# XILINX_ARTIX-7_FPGA_A704_Motherboard_CON.net
KiCad netlist of a schematic drawn in Altium Designer
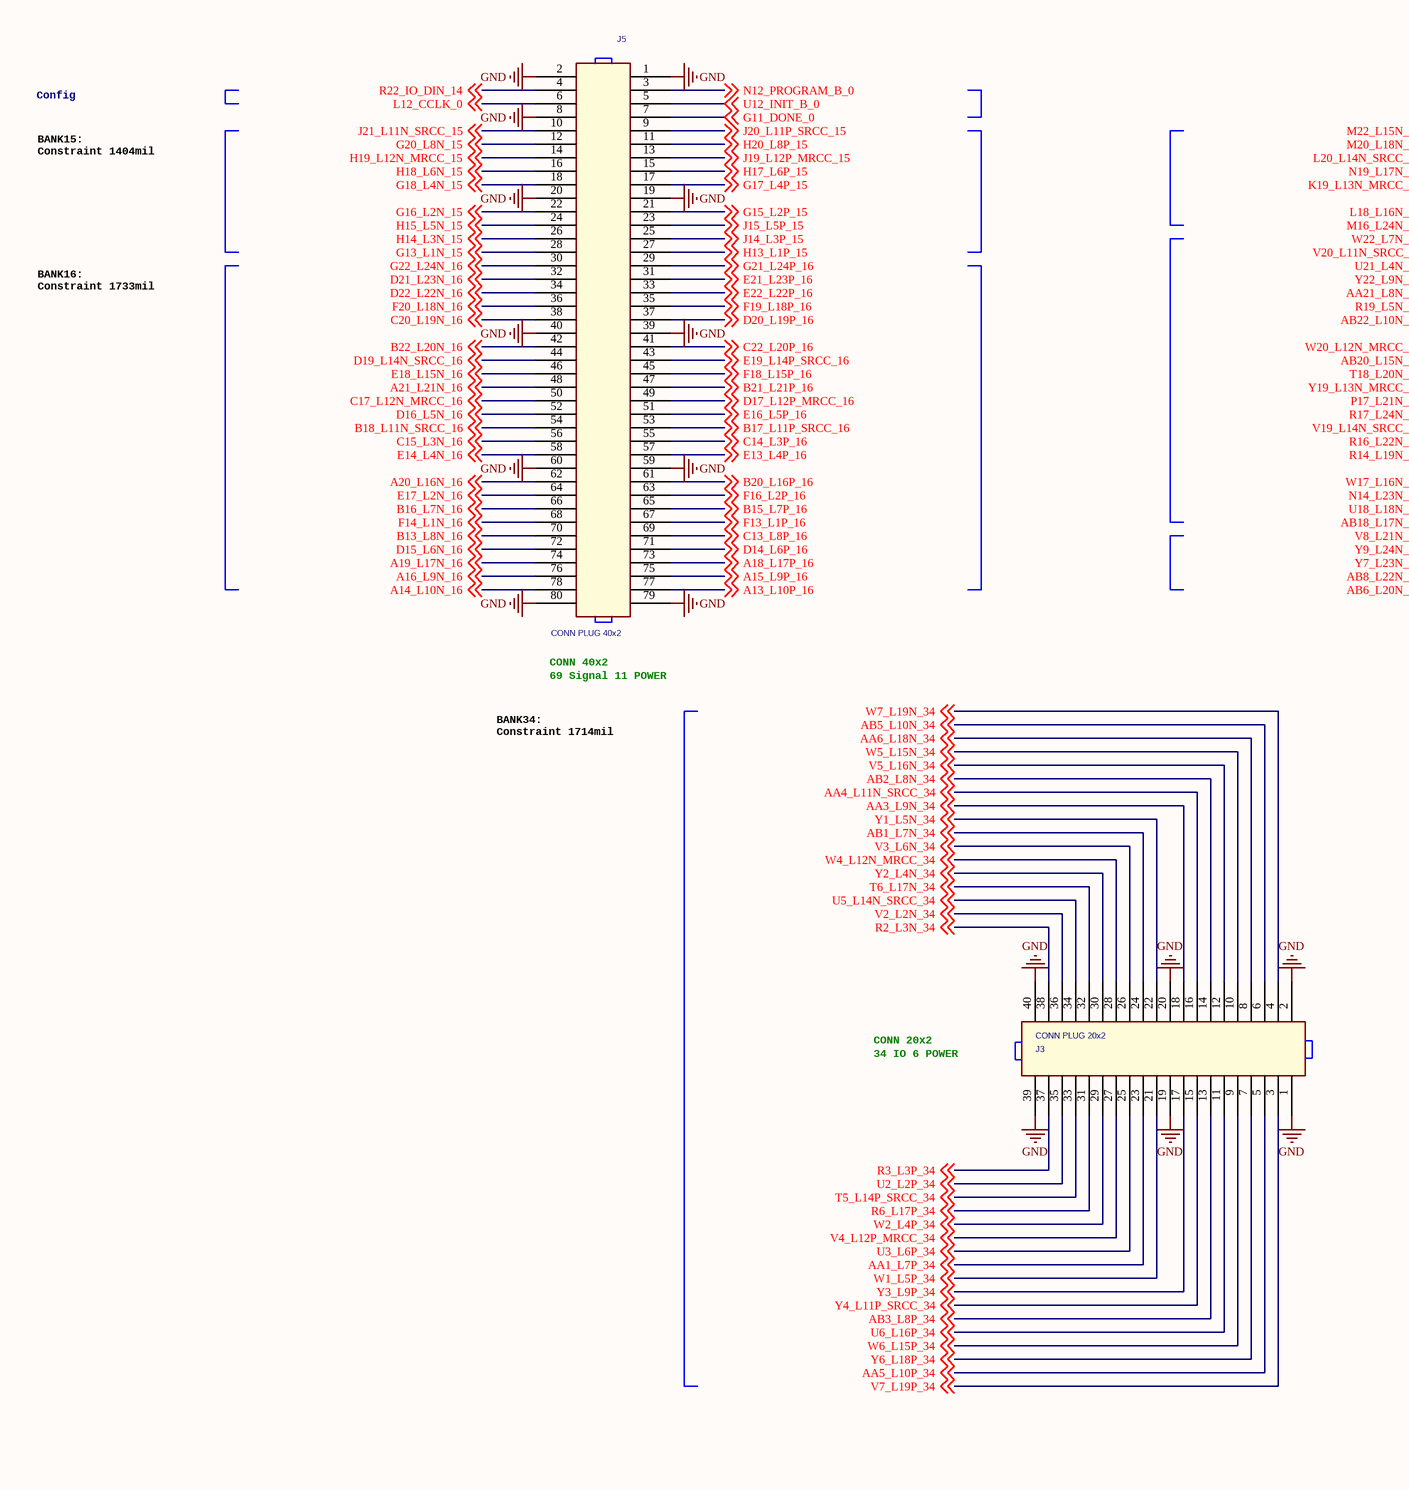
[diagram p0: XILINX ARTIX-7 FPGA A704 Motherboard_CON.SchDoc, left]
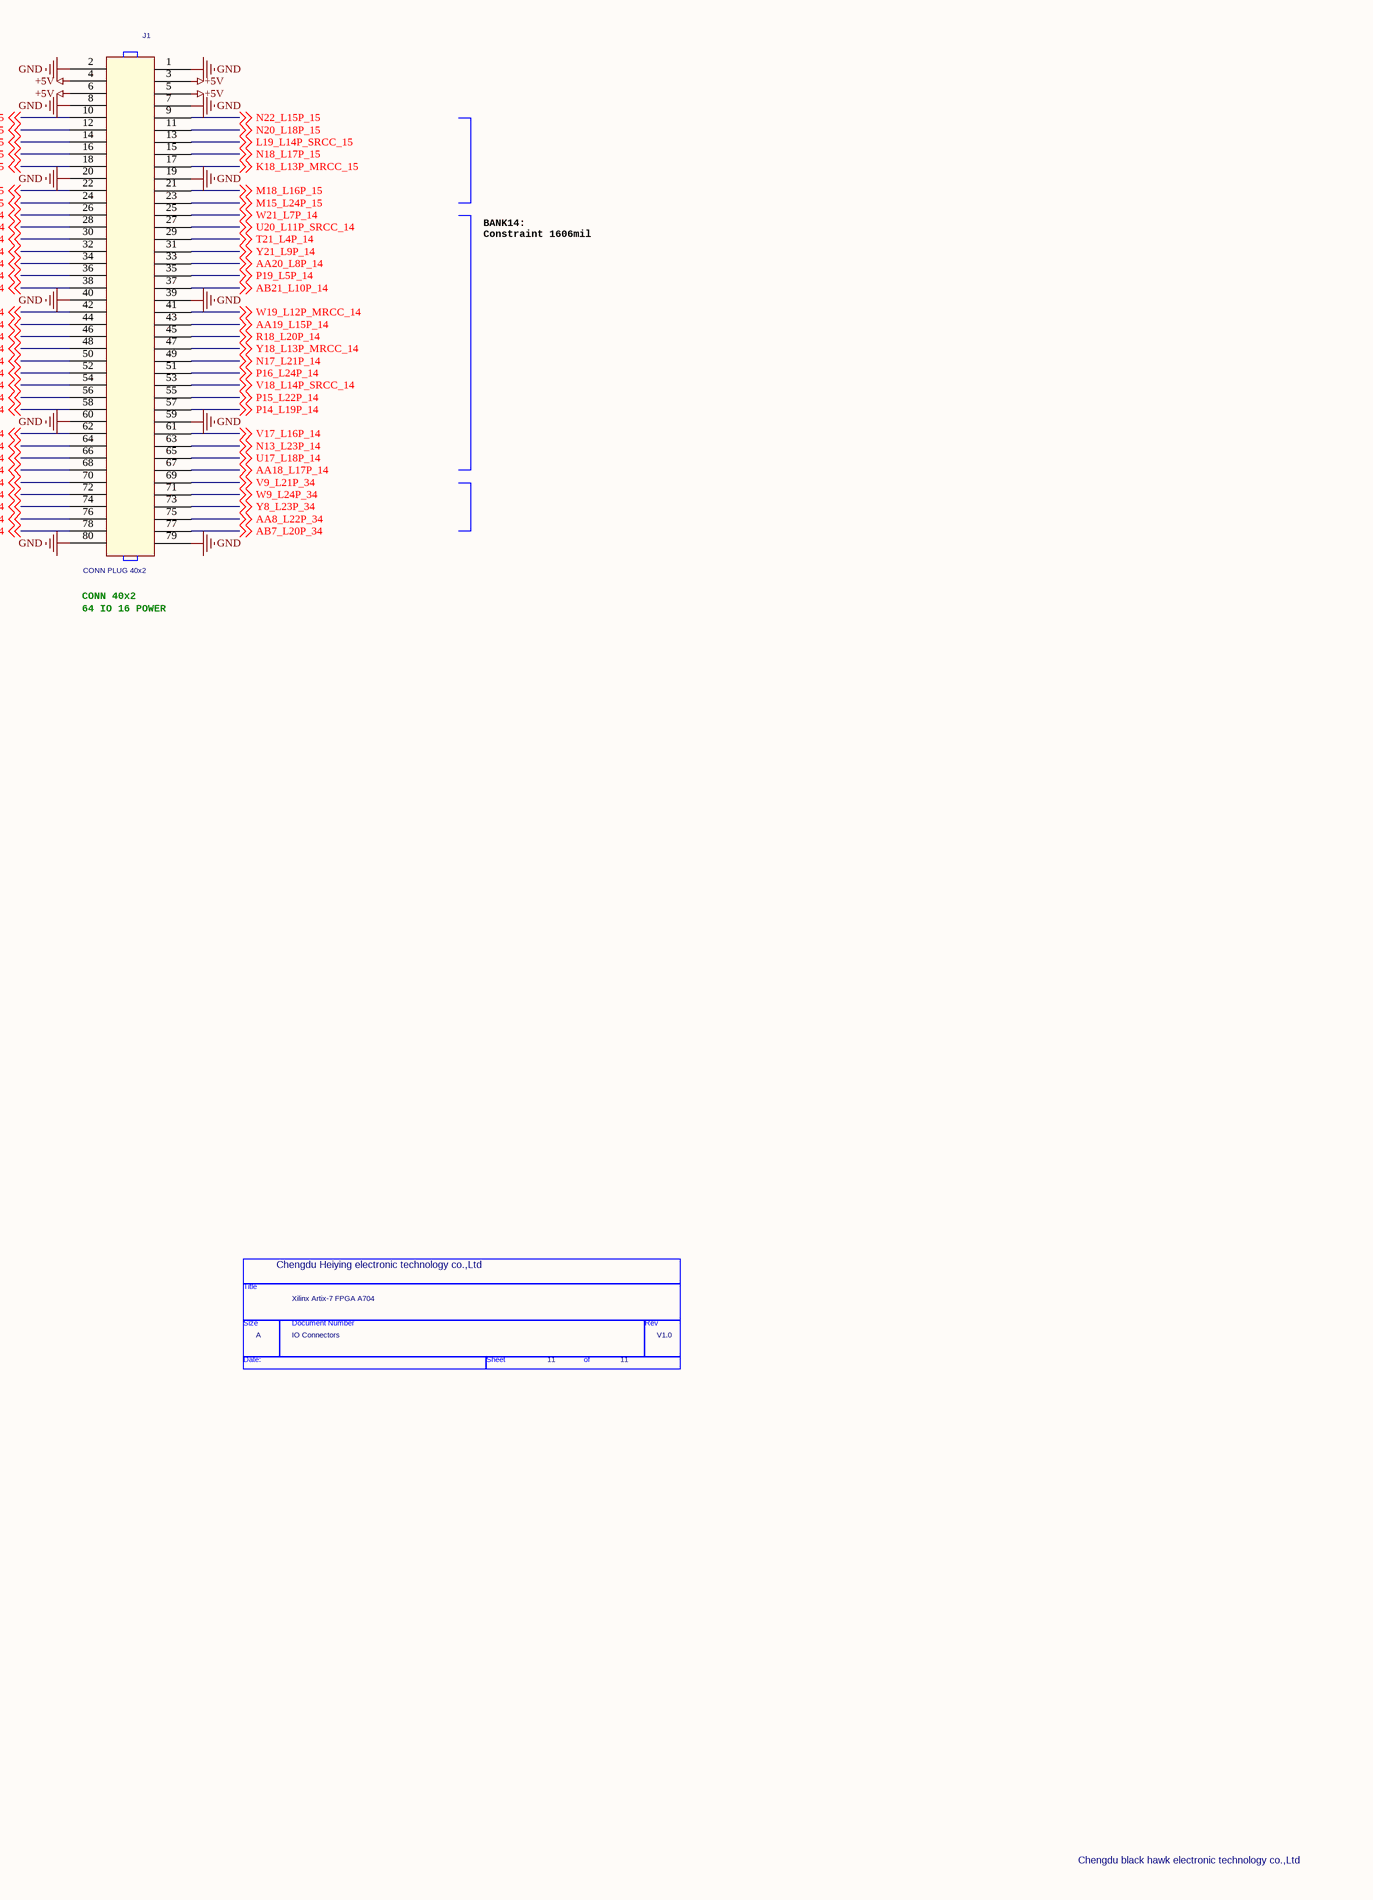
[diagram p1: XILINX ARTIX-7 FPGA A704 Motherboard_CON.SchDoc, right]

(export (version "E")
  (design (tool "Eeschema 10.0.6"))
  (components
    (comp (ref "*")
      (value "TitleBlock0")
      (fields
        (field (name "DOC") "IO Connectors")
        (field (name "REVCODE") "V1.0")
        (field (name "TITLE") "Xilinx Artix-7 FPGA A704")
        (field (name "PAGE SIZE") "A")
        (field (name "PAGE NUMBER") "11")
        (field (name "PAGE COUNT") "11")
      )
      (libsource (lib "*") (part "TitleBlock0"))
    )
    (comp (ref "J1") (value "CONN PLUG 40x2") (libsource (lib "*") (part "CONN PLUG 40x2")))
    (comp (ref "J3") (value "CONN PLUG 20x2") (libsource (lib "*") (part "CONN PLUG 20x2_0")))
    (comp (ref "J5") (value "CONN PLUG 40x2") (libsource (lib "*") (part "CONN PLUG 40x2")))
  )
  (nets
    (net (code "1") (name "+5V") (class "Default")
      (node (ref "J1") (pin "3") (pinfunction "3_3") (pintype "passive"))
      (node (ref "J1") (pin "4") (pinfunction "4_4") (pintype "passive"))
      (node (ref "J1") (pin "5") (pinfunction "5_5") (pintype "passive"))
      (node (ref "J1") (pin "6") (pinfunction "6_6") (pintype "passive"))
    )
    (net (code "2") (name "A13_L10P_16") (class "Default")
      (node (ref "J5") (pin "77") (pinfunction "77_77") (pintype "passive"))
    )
    (net (code "3") (name "A14_L10N_16") (class "Default")
      (node (ref "J5") (pin "78") (pinfunction "78_78") (pintype "passive"))
    )
    (net (code "4") (name "A15_L9P_16") (class "Default")
      (node (ref "J5") (pin "75") (pinfunction "75_75") (pintype "passive"))
    )
    (net (code "5") (name "A16_L9N_16") (class "Default")
      (node (ref "J5") (pin "76") (pinfunction "76_76") (pintype "passive"))
    )
    (net (code "6") (name "A18_L17P_16") (class "Default")
      (node (ref "J5") (pin "73") (pinfunction "73_73") (pintype "passive"))
    )
    (net (code "7") (name "A19_L17N_16") (class "Default")
      (node (ref "J5") (pin "74") (pinfunction "74_74") (pintype "passive"))
    )
    (net (code "8") (name "A20_L16N_16") (class "Default")
      (node (ref "J5") (pin "62") (pinfunction "62_62") (pintype "passive"))
    )
    (net (code "9") (name "A21_L21N_16") (class "Default")
      (node (ref "J5") (pin "48") (pinfunction "48_48") (pintype "passive"))
    )
    (net (code "10") (name "AA1_L7P_34") (class "Default")
      (node (ref "J3") (pin "23") (pinfunction "23_23") (pintype "passive"))
    )
    (net (code "11") (name "AA3_L9N_34") (class "Default")
      (node (ref "J3") (pin "18") (pinfunction "18_18") (pintype "passive"))
    )
    (net (code "12") (name "AA4_L11N_SRCC_34") (class "Default")
      (node (ref "J3") (pin "16") (pinfunction "16_16") (pintype "passive"))
    )
    (net (code "13") (name "AA5_L10P_34") (class "Default")
      (node (ref "J3") (pin "5") (pinfunction "5_5") (pintype "passive"))
    )
    (net (code "14") (name "AA6_L18N_34") (class "Default")
      (node (ref "J3") (pin "8") (pinfunction "8_8") (pintype "passive"))
    )
    (net (code "15") (name "AA8_L22P_34") (class "Default")
      (node (ref "J1") (pin "75") (pinfunction "75_75") (pintype "passive"))
    )
    (net (code "16") (name "AA18_L17P_14") (class "Default")
      (node (ref "J1") (pin "67") (pinfunction "67_67") (pintype "passive"))
    )
    (net (code "17") (name "AA19_L15P_14") (class "Default")
      (node (ref "J1") (pin "43") (pinfunction "43_43") (pintype "passive"))
    )
    (net (code "18") (name "AA20_L8P_14") (class "Default")
      (node (ref "J1") (pin "33") (pinfunction "33_33") (pintype "passive"))
    )
    (net (code "19") (name "AA21_L8N_14") (class "Default")
      (node (ref "J1") (pin "34") (pinfunction "34_34") (pintype "passive"))
    )
    (net (code "20") (name "AB1_L7N_34") (class "Default")
      (node (ref "J3") (pin "24") (pinfunction "24_24") (pintype "passive"))
    )
    (net (code "21") (name "AB2_L8N_34") (class "Default")
      (node (ref "J3") (pin "14") (pinfunction "14_14") (pintype "passive"))
    )
    (net (code "22") (name "AB3_L8P_34") (class "Default")
      (node (ref "J3") (pin "13") (pinfunction "13_13") (pintype "passive"))
    )
    (net (code "23") (name "AB5_L10N_34") (class "Default")
      (node (ref "J3") (pin "6") (pinfunction "6_6") (pintype "passive"))
    )
    (net (code "24") (name "AB6_L20N_34") (class "Default")
      (node (ref "J1") (pin "78") (pinfunction "78_78") (pintype "passive"))
    )
    (net (code "25") (name "AB7_L20P_34") (class "Default")
      (node (ref "J1") (pin "77") (pinfunction "77_77") (pintype "passive"))
    )
    (net (code "26") (name "AB8_L22N_34") (class "Default")
      (node (ref "J1") (pin "76") (pinfunction "76_76") (pintype "passive"))
    )
    (net (code "27") (name "AB18_L17N_14") (class "Default")
      (node (ref "J1") (pin "68") (pinfunction "68_68") (pintype "passive"))
    )
    (net (code "28") (name "AB20_L15N_14") (class "Default")
      (node (ref "J1") (pin "44") (pinfunction "44_44") (pintype "passive"))
    )
    (net (code "29") (name "AB21_L10P_14") (class "Default")
      (node (ref "J1") (pin "37") (pinfunction "37_37") (pintype "passive"))
    )
    (net (code "30") (name "AB22_L10N_14") (class "Default")
      (node (ref "J1") (pin "38") (pinfunction "38_38") (pintype "passive"))
    )
    (net (code "31") (name "B13_L8N_16") (class "Default")
      (node (ref "J5") (pin "70") (pinfunction "70_70") (pintype "passive"))
    )
    (net (code "32") (name "B15_L7P_16") (class "Default")
      (node (ref "J5") (pin "65") (pinfunction "65_65") (pintype "passive"))
    )
    (net (code "33") (name "B16_L7N_16") (class "Default")
      (node (ref "J5") (pin "66") (pinfunction "66_66") (pintype "passive"))
    )
    (net (code "34") (name "B17_L11P_SRCC_16") (class "Default")
      (node (ref "J5") (pin "53") (pinfunction "53_53") (pintype "passive"))
    )
    (net (code "35") (name "B18_L11N_SRCC_16") (class "Default")
      (node (ref "J5") (pin "54") (pinfunction "54_54") (pintype "passive"))
    )
    (net (code "36") (name "B20_L16P_16") (class "Default")
      (node (ref "J5") (pin "61") (pinfunction "61_61") (pintype "passive"))
    )
    (net (code "37") (name "B21_L21P_16") (class "Default")
      (node (ref "J5") (pin "47") (pinfunction "47_47") (pintype "passive"))
    )
    (net (code "38") (name "B22_L20N_16") (class "Default")
      (node (ref "J5") (pin "42") (pinfunction "42_42") (pintype "passive"))
    )
    (net (code "39") (name "C13_L8P_16") (class "Default")
      (node (ref "J5") (pin "69") (pinfunction "69_69") (pintype "passive"))
    )
    (net (code "40") (name "C14_L3P_16") (class "Default")
      (node (ref "J5") (pin "55") (pinfunction "55_55") (pintype "passive"))
    )
    (net (code "41") (name "C15_L3N_16") (class "Default")
      (node (ref "J5") (pin "56") (pinfunction "56_56") (pintype "passive"))
    )
    (net (code "42") (name "C17_L12N_MRCC_16") (class "Default")
      (node (ref "J5") (pin "50") (pinfunction "50_50") (pintype "passive"))
    )
    (net (code "43") (name "C20_L19N_16") (class "Default")
      (node (ref "J5") (pin "38") (pinfunction "38_38") (pintype "passive"))
    )
    (net (code "44") (name "C22_L20P_16") (class "Default")
      (node (ref "J5") (pin "41") (pinfunction "41_41") (pintype "passive"))
    )
    (net (code "45") (name "D14_L6P_16") (class "Default")
      (node (ref "J5") (pin "71") (pinfunction "71_71") (pintype "passive"))
    )
    (net (code "46") (name "D15_L6N_16") (class "Default")
      (node (ref "J5") (pin "72") (pinfunction "72_72") (pintype "passive"))
    )
    (net (code "47") (name "D16_L5N_16") (class "Default")
      (node (ref "J5") (pin "52") (pinfunction "52_52") (pintype "passive"))
    )
    (net (code "48") (name "D17_L12P_MRCC_16") (class "Default")
      (node (ref "J5") (pin "49") (pinfunction "49_49") (pintype "passive"))
    )
    (net (code "49") (name "D19_L14N_SRCC_16") (class "Default")
      (node (ref "J5") (pin "44") (pinfunction "44_44") (pintype "passive"))
    )
    (net (code "50") (name "D20_L19P_16") (class "Default")
      (node (ref "J5") (pin "37") (pinfunction "37_37") (pintype "passive"))
    )
    (net (code "51") (name "D21_L23N_16") (class "Default")
      (node (ref "J5") (pin "32") (pinfunction "32_32") (pintype "passive"))
    )
    (net (code "52") (name "D22_L22N_16") (class "Default")
      (node (ref "J5") (pin "34") (pinfunction "34_34") (pintype "passive"))
    )
    (net (code "53") (name "E13_L4P_16") (class "Default")
      (node (ref "J5") (pin "57") (pinfunction "57_57") (pintype "passive"))
    )
    (net (code "54") (name "E14_L4N_16") (class "Default")
      (node (ref "J5") (pin "58") (pinfunction "58_58") (pintype "passive"))
    )
    (net (code "55") (name "E16_L5P_16") (class "Default")
      (node (ref "J5") (pin "51") (pinfunction "51_51") (pintype "passive"))
    )
    (net (code "56") (name "E17_L2N_16") (class "Default")
      (node (ref "J5") (pin "64") (pinfunction "64_64") (pintype "passive"))
    )
    (net (code "57") (name "E18_L15N_16") (class "Default")
      (node (ref "J5") (pin "46") (pinfunction "46_46") (pintype "passive"))
    )
    (net (code "58") (name "E19_L14P_SRCC_16") (class "Default")
      (node (ref "J5") (pin "43") (pinfunction "43_43") (pintype "passive"))
    )
    (net (code "59") (name "E21_L23P_16") (class "Default")
      (node (ref "J5") (pin "31") (pinfunction "31_31") (pintype "passive"))
    )
    (net (code "60") (name "E22_L22P_16") (class "Default")
      (node (ref "J5") (pin "33") (pinfunction "33_33") (pintype "passive"))
    )
    (net (code "61") (name "F13_L1P_16") (class "Default")
      (node (ref "J5") (pin "67") (pinfunction "67_67") (pintype "passive"))
    )
    (net (code "62") (name "F14_L1N_16") (class "Default")
      (node (ref "J5") (pin "68") (pinfunction "68_68") (pintype "passive"))
    )
    (net (code "63") (name "F16_L2P_16") (class "Default")
      (node (ref "J5") (pin "63") (pinfunction "63_63") (pintype "passive"))
    )
    (net (code "64") (name "F18_L15P_16") (class "Default")
      (node (ref "J5") (pin "45") (pinfunction "45_45") (pintype "passive"))
    )
    (net (code "65") (name "F19_L18P_16") (class "Default")
      (node (ref "J5") (pin "35") (pinfunction "35_35") (pintype "passive"))
    )
    (net (code "66") (name "F20_L18N_16") (class "Default")
      (node (ref "J5") (pin "36") (pinfunction "36_36") (pintype "passive"))
    )
    (net (code "67") (name "G11_DONE_0") (class "Default")
      (node (ref "J5") (pin "7") (pinfunction "7_7") (pintype "passive"))
    )
    (net (code "68") (name "G13_L1N_15") (class "Default")
      (node (ref "J5") (pin "28") (pinfunction "28_28") (pintype "passive"))
    )
    (net (code "69") (name "G15_L2P_15") (class "Default")
      (node (ref "J5") (pin "21") (pinfunction "21_21") (pintype "passive"))
    )
    (net (code "70") (name "G16_L2N_15") (class "Default")
      (node (ref "J5") (pin "22") (pinfunction "22_22") (pintype "passive"))
    )
    (net (code "71") (name "G17_L4P_15") (class "Default")
      (node (ref "J5") (pin "17") (pinfunction "17_17") (pintype "passive"))
    )
    (net (code "72") (name "G18_L4N_15") (class "Default")
      (node (ref "J5") (pin "18") (pinfunction "18_18") (pintype "passive"))
    )
    (net (code "73") (name "G20_L8N_15") (class "Default")
      (node (ref "J5") (pin "12") (pinfunction "12_12") (pintype "passive"))
    )
    (net (code "74") (name "G21_L24P_16") (class "Default")
      (node (ref "J5") (pin "29") (pinfunction "29_29") (pintype "passive"))
    )
    (net (code "75") (name "G22_L24N_16") (class "Default")
      (node (ref "J5") (pin "30") (pinfunction "30_30") (pintype "passive"))
    )
    (net (code "76") (name "GND") (class "Default")
      (node (ref "J1") (pin "1") (pinfunction "1_1") (pintype "passive"))
      (node (ref "J1") (pin "19") (pinfunction "19_19") (pintype "passive"))
      (node (ref "J1") (pin "2") (pinfunction "2_2") (pintype "passive"))
      (node (ref "J1") (pin "20") (pinfunction "20_20") (pintype "passive"))
      (node (ref "J1") (pin "39") (pinfunction "39_39") (pintype "passive"))
      (node (ref "J1") (pin "40") (pinfunction "40_40") (pintype "passive"))
      (node (ref "J1") (pin "59") (pinfunction "59_59") (pintype "passive"))
      (node (ref "J1") (pin "60") (pinfunction "60_60") (pintype "passive"))
      (node (ref "J1") (pin "7") (pinfunction "7_7") (pintype "passive"))
      (node (ref "J1") (pin "79") (pinfunction "79_79") (pintype "passive"))
      (node (ref "J1") (pin "8") (pinfunction "8_8") (pintype "passive"))
      (node (ref "J1") (pin "80") (pinfunction "80_80") (pintype "passive"))
      (node (ref "J3") (pin "1") (pinfunction "1_1") (pintype "passive"))
      (node (ref "J3") (pin "19") (pinfunction "19_19") (pintype "passive"))
      (node (ref "J3") (pin "2") (pinfunction "2_2") (pintype "passive"))
      (node (ref "J3") (pin "20") (pinfunction "20_20") (pintype "passive"))
      (node (ref "J3") (pin "39") (pinfunction "39_39") (pintype "passive"))
      (node (ref "J3") (pin "40") (pinfunction "40_40") (pintype "passive"))
      (node (ref "J5") (pin "1") (pinfunction "1_1") (pintype "passive"))
      (node (ref "J5") (pin "19") (pinfunction "19_19") (pintype "passive"))
      (node (ref "J5") (pin "2") (pinfunction "2_2") (pintype "passive"))
      (node (ref "J5") (pin "20") (pinfunction "20_20") (pintype "passive"))
      (node (ref "J5") (pin "39") (pinfunction "39_39") (pintype "passive"))
      (node (ref "J5") (pin "40") (pinfunction "40_40") (pintype "passive"))
      (node (ref "J5") (pin "59") (pinfunction "59_59") (pintype "passive"))
      (node (ref "J5") (pin "60") (pinfunction "60_60") (pintype "passive"))
      (node (ref "J5") (pin "79") (pinfunction "79_79") (pintype "passive"))
      (node (ref "J5") (pin "8") (pinfunction "8_8") (pintype "passive"))
      (node (ref "J5") (pin "80") (pinfunction "80_80") (pintype "passive"))
    )
    (net (code "77") (name "H13_L1P_15") (class "Default")
      (node (ref "J5") (pin "27") (pinfunction "27_27") (pintype "passive"))
    )
    (net (code "78") (name "H14_L3N_15") (class "Default")
      (node (ref "J5") (pin "26") (pinfunction "26_26") (pintype "passive"))
    )
    (net (code "79") (name "H15_L5N_15") (class "Default")
      (node (ref "J5") (pin "24") (pinfunction "24_24") (pintype "passive"))
    )
    (net (code "80") (name "H17_L6P_15") (class "Default")
      (node (ref "J5") (pin "15") (pinfunction "15_15") (pintype "passive"))
    )
    (net (code "81") (name "H18_L6N_15") (class "Default")
      (node (ref "J5") (pin "16") (pinfunction "16_16") (pintype "passive"))
    )
    (net (code "82") (name "H19_L12N_MRCC_15") (class "Default")
      (node (ref "J5") (pin "14") (pinfunction "14_14") (pintype "passive"))
    )
    (net (code "83") (name "H20_L8P_15") (class "Default")
      (node (ref "J5") (pin "11") (pinfunction "11_11") (pintype "passive"))
    )
    (net (code "84") (name "J14_L3P_15") (class "Default")
      (node (ref "J5") (pin "25") (pinfunction "25_25") (pintype "passive"))
    )
    (net (code "85") (name "J15_L5P_15") (class "Default")
      (node (ref "J5") (pin "23") (pinfunction "23_23") (pintype "passive"))
    )
    (net (code "86") (name "J19_L12P_MRCC_15") (class "Default")
      (node (ref "J5") (pin "13") (pinfunction "13_13") (pintype "passive"))
    )
    (net (code "87") (name "J20_L11P_SRCC_15") (class "Default")
      (node (ref "J5") (pin "9") (pinfunction "9_9") (pintype "passive"))
    )
    (net (code "88") (name "J21_L11N_SRCC_15") (class "Default")
      (node (ref "J5") (pin "10") (pinfunction "10_10") (pintype "passive"))
    )
    (net (code "89") (name "K18_L13P_MRCC_15") (class "Default")
      (node (ref "J1") (pin "17") (pinfunction "17_17") (pintype "passive"))
    )
    (net (code "90") (name "K19_L13N_MRCC_15") (class "Default")
      (node (ref "J1") (pin "18") (pinfunction "18_18") (pintype "passive"))
    )
    (net (code "91") (name "L12_CCLK_0") (class "Default")
      (node (ref "J5") (pin "6") (pinfunction "6_6") (pintype "passive"))
    )
    (net (code "92") (name "L18_L16N_15") (class "Default")
      (node (ref "J1") (pin "22") (pinfunction "22_22") (pintype "passive"))
    )
    (net (code "93") (name "L19_L14P_SRCC_15") (class "Default")
      (node (ref "J1") (pin "13") (pinfunction "13_13") (pintype "passive"))
    )
    (net (code "94") (name "L20_L14N_SRCC_15") (class "Default")
      (node (ref "J1") (pin "14") (pinfunction "14_14") (pintype "passive"))
    )
    (net (code "95") (name "M15_L24P_15") (class "Default")
      (node (ref "J1") (pin "23") (pinfunction "23_23") (pintype "passive"))
    )
    (net (code "96") (name "M16_L24N_15") (class "Default")
      (node (ref "J1") (pin "24") (pinfunction "24_24") (pintype "passive"))
    )
    (net (code "97") (name "M18_L16P_15") (class "Default")
      (node (ref "J1") (pin "21") (pinfunction "21_21") (pintype "passive"))
    )
    (net (code "98") (name "M20_L18N_15") (class "Default")
      (node (ref "J1") (pin "12") (pinfunction "12_12") (pintype "passive"))
    )
    (net (code "99") (name "M22_L15N_15") (class "Default")
      (node (ref "J1") (pin "10") (pinfunction "10_10") (pintype "passive"))
    )
    (net (code "100") (name "N12_PROGRAM_B_0") (class "Default")
      (node (ref "J5") (pin "3") (pinfunction "3_3") (pintype "passive"))
    )
    (net (code "101") (name "N13_L23P_14") (class "Default")
      (node (ref "J1") (pin "63") (pinfunction "63_63") (pintype "passive"))
    )
    (net (code "102") (name "N14_L23N_14") (class "Default")
      (node (ref "J1") (pin "64") (pinfunction "64_64") (pintype "passive"))
    )
    (net (code "103") (name "N17_L21P_14") (class "Default")
      (node (ref "J1") (pin "49") (pinfunction "49_49") (pintype "passive"))
    )
    (net (code "104") (name "N18_L17P_15") (class "Default")
      (node (ref "J1") (pin "15") (pinfunction "15_15") (pintype "passive"))
    )
    (net (code "105") (name "N19_L17N_15") (class "Default")
      (node (ref "J1") (pin "16") (pinfunction "16_16") (pintype "passive"))
    )
    (net (code "106") (name "N20_L18P_15") (class "Default")
      (node (ref "J1") (pin "11") (pinfunction "11_11") (pintype "passive"))
    )
    (net (code "107") (name "N22_L15P_15") (class "Default")
      (node (ref "J1") (pin "9") (pinfunction "9_9") (pintype "passive"))
    )
    (net (code "108") (name "P14_L19P_14") (class "Default")
      (node (ref "J1") (pin "57") (pinfunction "57_57") (pintype "passive"))
    )
    (net (code "109") (name "P15_L22P_14") (class "Default")
      (node (ref "J1") (pin "55") (pinfunction "55_55") (pintype "passive"))
    )
    (net (code "110") (name "P16_L24P_14") (class "Default")
      (node (ref "J1") (pin "51") (pinfunction "51_51") (pintype "passive"))
    )
    (net (code "111") (name "P17_L21N_14") (class "Default")
      (node (ref "J1") (pin "50") (pinfunction "50_50") (pintype "passive"))
    )
    (net (code "112") (name "P19_L5P_14") (class "Default")
      (node (ref "J1") (pin "35") (pinfunction "35_35") (pintype "passive"))
    )
    (net (code "113") (name "R2_L3N_34") (class "Default")
      (node (ref "J3") (pin "38") (pinfunction "38_38") (pintype "passive"))
    )
    (net (code "114") (name "R3_L3P_34") (class "Default")
      (node (ref "J3") (pin "37") (pinfunction "37_37") (pintype "passive"))
    )
    (net (code "115") (name "R6_L17P_34") (class "Default")
      (node (ref "J3") (pin "31") (pinfunction "31_31") (pintype "passive"))
    )
    (net (code "116") (name "R14_L19N_14") (class "Default")
      (node (ref "J1") (pin "58") (pinfunction "58_58") (pintype "passive"))
    )
    (net (code "117") (name "R16_L22N_14") (class "Default")
      (node (ref "J1") (pin "56") (pinfunction "56_56") (pintype "passive"))
    )
    (net (code "118") (name "R17_L24N_14") (class "Default")
      (node (ref "J1") (pin "52") (pinfunction "52_52") (pintype "passive"))
    )
    (net (code "119") (name "R18_L20P_14") (class "Default")
      (node (ref "J1") (pin "45") (pinfunction "45_45") (pintype "passive"))
    )
    (net (code "120") (name "R19_L5N_14") (class "Default")
      (node (ref "J1") (pin "36") (pinfunction "36_36") (pintype "passive"))
    )
    (net (code "121") (name "R22_IO_DIN_14") (class "Default")
      (node (ref "J5") (pin "4") (pinfunction "4_4") (pintype "passive"))
    )
    (net (code "122") (name "T5_L14P_SRCC_34") (class "Default")
      (node (ref "J3") (pin "33") (pinfunction "33_33") (pintype "passive"))
    )
    (net (code "123") (name "T6_L17N_34") (class "Default")
      (node (ref "J3") (pin "32") (pinfunction "32_32") (pintype "passive"))
    )
    (net (code "124") (name "T18_L20N_14") (class "Default")
      (node (ref "J1") (pin "46") (pinfunction "46_46") (pintype "passive"))
    )
    (net (code "125") (name "T21_L4P_14") (class "Default")
      (node (ref "J1") (pin "29") (pinfunction "29_29") (pintype "passive"))
    )
    (net (code "126") (name "U2_L2P_34") (class "Default")
      (node (ref "J3") (pin "35") (pinfunction "35_35") (pintype "passive"))
    )
    (net (code "127") (name "U3_L6P_34") (class "Default")
      (node (ref "J3") (pin "25") (pinfunction "25_25") (pintype "passive"))
    )
    (net (code "128") (name "U5_L14N_SRCC_34") (class "Default")
      (node (ref "J3") (pin "34") (pinfunction "34_34") (pintype "passive"))
    )
    (net (code "129") (name "U6_L16P_34") (class "Default")
      (node (ref "J3") (pin "11") (pinfunction "11_11") (pintype "passive"))
    )
    (net (code "130") (name "U12_INIT_B_0") (class "Default")
      (node (ref "J5") (pin "5") (pinfunction "5_5") (pintype "passive"))
    )
    (net (code "131") (name "U17_L18P_14") (class "Default")
      (node (ref "J1") (pin "65") (pinfunction "65_65") (pintype "passive"))
    )
    (net (code "132") (name "U18_L18N_14") (class "Default")
      (node (ref "J1") (pin "66") (pinfunction "66_66") (pintype "passive"))
    )
    (net (code "133") (name "U20_L11P_SRCC_14") (class "Default")
      (node (ref "J1") (pin "27") (pinfunction "27_27") (pintype "passive"))
    )
    (net (code "134") (name "U21_L4N_14") (class "Default")
      (node (ref "J1") (pin "30") (pinfunction "30_30") (pintype "passive"))
    )
    (net (code "135") (name "V2_L2N_34") (class "Default")
      (node (ref "J3") (pin "36") (pinfunction "36_36") (pintype "passive"))
    )
    (net (code "136") (name "V3_L6N_34") (class "Default")
      (node (ref "J3") (pin "26") (pinfunction "26_26") (pintype "passive"))
    )
    (net (code "137") (name "V4_L12P_MRCC_34") (class "Default")
      (node (ref "J3") (pin "27") (pinfunction "27_27") (pintype "passive"))
    )
    (net (code "138") (name "V5_L16N_34") (class "Default")
      (node (ref "J3") (pin "12") (pinfunction "12_12") (pintype "passive"))
    )
    (net (code "139") (name "V7_L19P_34") (class "Default")
      (node (ref "J3") (pin "3") (pinfunction "3_3") (pintype "passive"))
    )
    (net (code "140") (name "V8_L21N_34") (class "Default")
      (node (ref "J1") (pin "70") (pinfunction "70_70") (pintype "passive"))
    )
    (net (code "141") (name "V9_L21P_34") (class "Default")
      (node (ref "J1") (pin "69") (pinfunction "69_69") (pintype "passive"))
    )
    (net (code "142") (name "V17_L16P_14") (class "Default")
      (node (ref "J1") (pin "61") (pinfunction "61_61") (pintype "passive"))
    )
    (net (code "143") (name "V18_L14P_SRCC_14") (class "Default")
      (node (ref "J1") (pin "53") (pinfunction "53_53") (pintype "passive"))
    )
    (net (code "144") (name "V19_L14N_SRCC_14") (class "Default")
      (node (ref "J1") (pin "54") (pinfunction "54_54") (pintype "passive"))
    )
    (net (code "145") (name "V20_L11N_SRCC_14") (class "Default")
      (node (ref "J1") (pin "28") (pinfunction "28_28") (pintype "passive"))
    )
    (net (code "146") (name "W1_L5P_34") (class "Default")
      (node (ref "J3") (pin "21") (pinfunction "21_21") (pintype "passive"))
    )
    (net (code "147") (name "W2_L4P_34") (class "Default")
      (node (ref "J3") (pin "29") (pinfunction "29_29") (pintype "passive"))
    )
    (net (code "148") (name "W4_L12N_MRCC_34") (class "Default")
      (node (ref "J3") (pin "28") (pinfunction "28_28") (pintype "passive"))
    )
    (net (code "149") (name "W5_L15N_34") (class "Default")
      (node (ref "J3") (pin "10") (pinfunction "10_10") (pintype "passive"))
    )
    (net (code "150") (name "W6_L15P_34") (class "Default")
      (node (ref "J3") (pin "9") (pinfunction "9_9") (pintype "passive"))
    )
    (net (code "151") (name "W7_L19N_34") (class "Default")
      (node (ref "J3") (pin "4") (pinfunction "4_4") (pintype "passive"))
    )
    (net (code "152") (name "W9_L24P_34") (class "Default")
      (node (ref "J1") (pin "71") (pinfunction "71_71") (pintype "passive"))
    )
    (net (code "153") (name "W17_L16N_14") (class "Default")
      (node (ref "J1") (pin "62") (pinfunction "62_62") (pintype "passive"))
    )
    (net (code "154") (name "W19_L12P_MRCC_14") (class "Default")
      (node (ref "J1") (pin "41") (pinfunction "41_41") (pintype "passive"))
    )
    (net (code "155") (name "W20_L12N_MRCC_14") (class "Default")
      (node (ref "J1") (pin "42") (pinfunction "42_42") (pintype "passive"))
    )
    (net (code "156") (name "W21_L7P_14") (class "Default")
      (node (ref "J1") (pin "25") (pinfunction "25_25") (pintype "passive"))
    )
    (net (code "157") (name "W22_L7N_14") (class "Default")
      (node (ref "J1") (pin "26") (pinfunction "26_26") (pintype "passive"))
    )
    (net (code "158") (name "Y1_L5N_34") (class "Default")
      (node (ref "J3") (pin "22") (pinfunction "22_22") (pintype "passive"))
    )
    (net (code "159") (name "Y2_L4N_34") (class "Default")
      (node (ref "J3") (pin "30") (pinfunction "30_30") (pintype "passive"))
    )
    (net (code "160") (name "Y3_L9P_34") (class "Default")
      (node (ref "J3") (pin "17") (pinfunction "17_17") (pintype "passive"))
    )
    (net (code "161") (name "Y4_L11P_SRCC_34") (class "Default")
      (node (ref "J3") (pin "15") (pinfunction "15_15") (pintype "passive"))
    )
    (net (code "162") (name "Y6_L18P_34") (class "Default")
      (node (ref "J3") (pin "7") (pinfunction "7_7") (pintype "passive"))
    )
    (net (code "163") (name "Y7_L23N_34") (class "Default")
      (node (ref "J1") (pin "74") (pinfunction "74_74") (pintype "passive"))
    )
    (net (code "164") (name "Y8_L23P_34") (class "Default")
      (node (ref "J1") (pin "73") (pinfunction "73_73") (pintype "passive"))
    )
    (net (code "165") (name "Y9_L24N_34") (class "Default")
      (node (ref "J1") (pin "72") (pinfunction "72_72") (pintype "passive"))
    )
    (net (code "166") (name "Y18_L13P_MRCC_14") (class "Default")
      (node (ref "J1") (pin "47") (pinfunction "47_47") (pintype "passive"))
    )
    (net (code "167") (name "Y19_L13N_MRCC_14") (class "Default")
      (node (ref "J1") (pin "48") (pinfunction "48_48") (pintype "passive"))
    )
    (net (code "168") (name "Y21_L9P_14") (class "Default")
      (node (ref "J1") (pin "31") (pinfunction "31_31") (pintype "passive"))
    )
    (net (code "169") (name "Y22_L9N_14") (class "Default")
      (node (ref "J1") (pin "32") (pinfunction "32_32") (pintype "passive"))
    )
  )
)
